# KX1_DB_DAC_2.net
KiCad netlist of a schematic drawn in Altium Designer
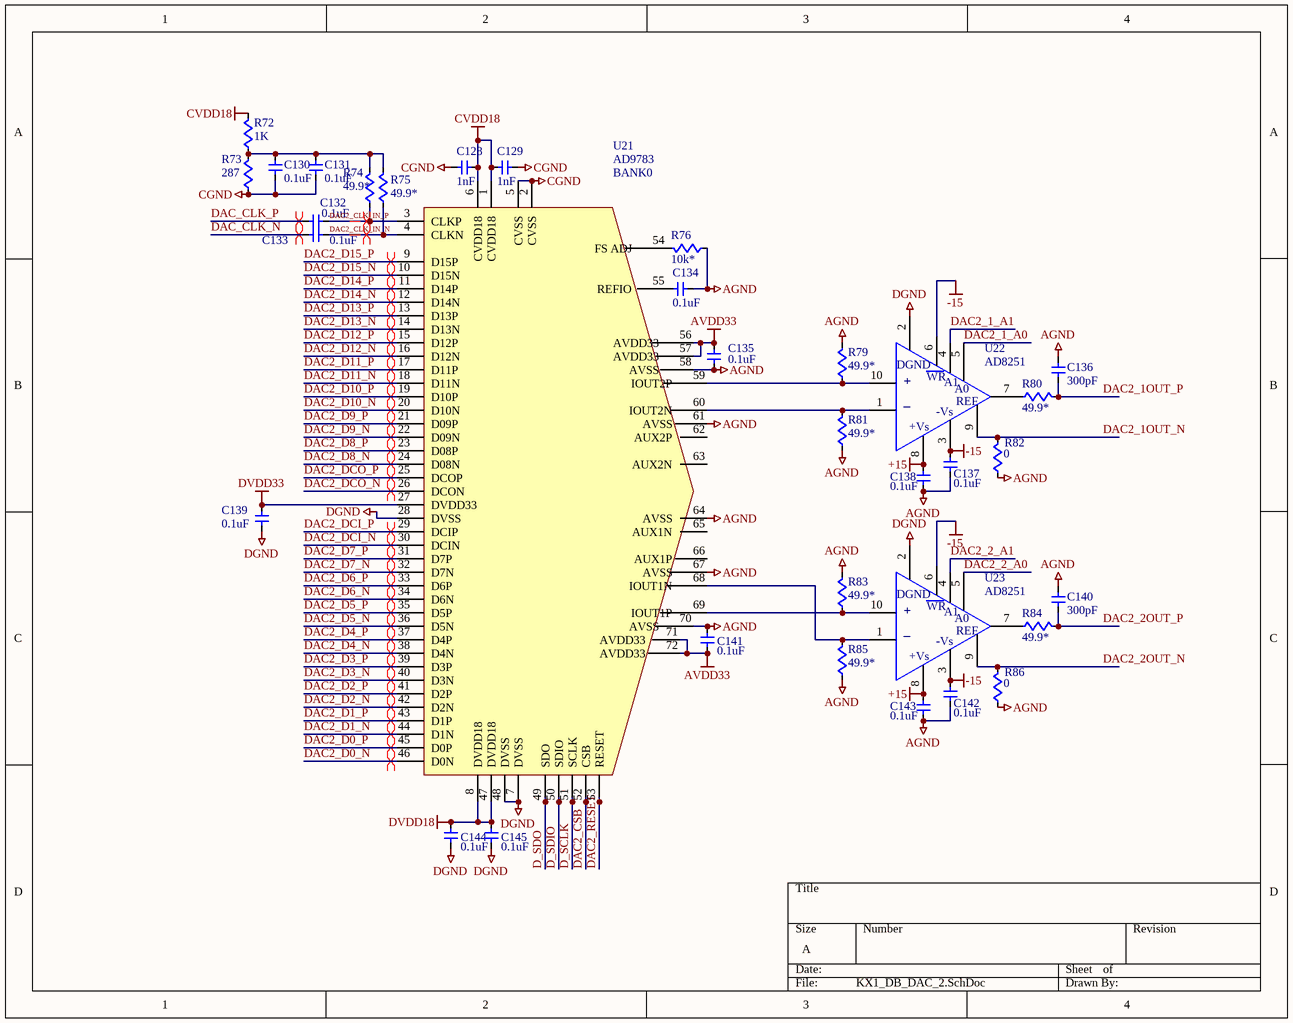
[diagram p0: KX1_DB_DAC_2.SchDoc]

(export (version "E")
  (design (tool "Eeschema 10.0.6"))
  (components
    (comp (ref "C128")
      (value "1nF")
      (footprint "0603w")
      (description "capacitor")
      (fields
        (field (name "MANUFACTURER") "Murata Electronics North America")
        (field (name "MANUFACTURER PART NUMBER") "GRM188R71H102KA01D")
      )
      (libsource (lib "KX1_DB") (part "CAP_SM_1"))
    )
    (comp (ref "C129")
      (value "1nF")
      (footprint "0603w")
      (description "capacitor")
      (fields
        (field (name "MANUFACTURER") "Murata Electronics North America")
        (field (name "MANUFACTURER PART NUMBER") "GRM188R71H102KA01D")
      )
      (libsource (lib "KX1_DB") (part "CAP_SM_1"))
    )
    (comp (ref "C130")
      (value "0.1uF")
      (footprint "0603w")
      (description "capacitor")
      (fields
        (field (name "MANUFACTURER") "Kemet")
        (field (name "MANUFACTURER PART NUMBER") "C0603C104K3RACTU")
      )
      (libsource (lib "KX1_DB") (part "CAP_SM"))
    )
    (comp (ref "C131")
      (value "0.1uF")
      (footprint "0603w")
      (description "capacitor")
      (fields
        (field (name "MANUFACTURER") "Kemet")
        (field (name "MANUFACTURER PART NUMBER") "C0603C104K3RACTU")
      )
      (libsource (lib "KX1_DB") (part "CAP_SM"))
    )
    (comp (ref "C132")
      (value "0.1uF")
      (footprint "1206")
      (description "capacitor")
      (fields
        (field (name "MANUFACTURER") "Murata Electronics North America")
        (field (name "MANUFACTURER PART NUMBER") "GRM31C5C1E104JA01L")
      )
      (libsource (lib "KX1_DB") (part "CAP_SM_1"))
    )
    (comp (ref "C133")
      (value "0.1uF")
      (footprint "1206")
      (description "capacitor")
      (fields
        (field (name "MANUFACTURER") "Murata Electronics North America")
        (field (name "MANUFACTURER PART NUMBER") "GRM31C5C1E104JA01L")
      )
      (libsource (lib "KX1_DB") (part "CAP_SM_1"))
    )
    (comp (ref "C134")
      (value "0.1uF")
      (footprint "0603w")
      (description "capacitor")
      (fields
        (field (name "MANUFACTURER") "Kemet")
        (field (name "MANUFACTURER PART NUMBER") "C0603C104K3RACTU")
      )
      (libsource (lib "KX1_DB") (part "CAP_SM_1"))
    )
    (comp (ref "C135")
      (value "0.1uF")
      (footprint "0603w")
      (description "capacitor")
      (fields
        (field (name "MANUFACTURER") "Kemet")
        (field (name "MANUFACTURER PART NUMBER") "C0603C104K3RACTU")
      )
      (libsource (lib "KX1_DB") (part "CAP_SM_1"))
    )
    (comp (ref "C136")
      (value "300pF")
      (footprint "0603w")
      (description "capacitor")
      (libsource (lib "KX1_DB") (part "CAP_SM_1"))
    )
    (comp (ref "C137")
      (value "0.1uF")
      (footprint "0603w")
      (description "capacitor")
      (fields
        (field (name "MANUFACTURER") "Kemet")
        (field (name "MANUFACTURER PART NUMBER") "C0603C104K3RACTU")
      )
      (libsource (lib "KX1_DB") (part "CAP_SM_1"))
    )
    (comp (ref "C138")
      (value "0.1uF")
      (footprint "0603w")
      (description "capacitor")
      (fields
        (field (name "MANUFACTURER") "Kemet")
        (field (name "MANUFACTURER PART NUMBER") "C0603C104K3RACTU")
      )
      (libsource (lib "KX1_DB") (part "CAP_SM_1"))
    )
    (comp (ref "C139")
      (value "0.1uF")
      (footprint "0603w")
      (description "capacitor")
      (fields
        (field (name "MANUFACTURER") "Kemet")
        (field (name "MANUFACTURER PART NUMBER") "C0603C104K3RACTU")
      )
      (libsource (lib "KX1_DB") (part "CAP_SM_1"))
    )
    (comp (ref "C140")
      (value "300pF")
      (footprint "0603w")
      (description "capacitor")
      (libsource (lib "KX1_DB") (part "CAP_SM_1"))
    )
    (comp (ref "C141")
      (value "0.1uF")
      (footprint "0603w")
      (description "capacitor")
      (fields
        (field (name "MANUFACTURER") "Kemet")
        (field (name "MANUFACTURER PART NUMBER") "C0603C104K3RACTU")
      )
      (libsource (lib "KX1_DB") (part "CAP_SM_1"))
    )
    (comp (ref "C142")
      (value "0.1uF")
      (footprint "0603w")
      (description "capacitor")
      (fields
        (field (name "MANUFACTURER") "Kemet")
        (field (name "MANUFACTURER PART NUMBER") "C0603C104K3RACTU")
      )
      (libsource (lib "KX1_DB") (part "CAP_SM_1"))
    )
    (comp (ref "C143")
      (value "0.1uF")
      (footprint "0603w")
      (description "capacitor")
      (fields
        (field (name "MANUFACTURER") "Kemet")
        (field (name "MANUFACTURER PART NUMBER") "C0603C104K3RACTU")
      )
      (libsource (lib "KX1_DB") (part "CAP_SM_1"))
    )
    (comp (ref "C144")
      (value "0.1uF")
      (footprint "0603w")
      (description "capacitor")
      (fields
        (field (name "MANUFACTURER") "Kemet")
        (field (name "MANUFACTURER PART NUMBER") "C0603C104K3RACTU")
      )
      (libsource (lib "KX1_DB") (part "CAP_SM_1"))
    )
    (comp (ref "C145")
      (value "0.1uF")
      (footprint "0603w")
      (description "capacitor")
      (fields
        (field (name "MANUFACTURER") "Kemet")
        (field (name "MANUFACTURER PART NUMBER") "C0603C104K3RACTU")
      )
      (libsource (lib "KX1_DB") (part "CAP_SM_1"))
    )
    (comp (ref "R72")
      (value "1K")
      (footprint "0603w")
      (description "resistor")
      (fields
        (field (name "MANUFACTURER") "Yageo")
        (field (name "MANUFACTURER PART NUMBER") "RC0603FR-071KL")
      )
      (libsource (lib "KX1_DB") (part "RES_SM"))
    )
    (comp (ref "R73")
      (value "287")
      (footprint "0603w")
      (description "resistor")
      (fields
        (field (name "MANUFACTURER") "Yageo")
        (field (name "MANUFACTURER PART NUMBER") "RC0603FR-07287RL")
      )
      (libsource (lib "KX1_DB") (part "RES_SM"))
    )
    (comp (ref "R74")
      (value "49.9*")
      (footprint "0603w")
      (description "resistor")
      (fields
        (field (name "MANUFACTURER") "Stackpole Electronics Inc")
        (field (name "MANUFACTURER PART NUMBER") "RNCS0603BKE49R9")
      )
      (libsource (lib "KX1_DB") (part "RES_SM"))
    )
    (comp (ref "R75")
      (value "49.9*")
      (footprint "0603w")
      (description "resistor")
      (fields
        (field (name "MANUFACTURER") "Stackpole Electronics Inc")
        (field (name "MANUFACTURER PART NUMBER") "RNCS0603BKE49R9")
      )
      (libsource (lib "KX1_DB") (part "RES_SM"))
    )
    (comp (ref "R76")
      (value "10k*")
      (footprint "0603w")
      (description "resistor")
      (fields
        (field (name "MANUFACTURER") "Susumu")
        (field (name "MANUFACTURER PART NUMBER") "RG1608P-103-B-T5")
      )
      (libsource (lib "KX1_DB") (part "RES_SM"))
    )
    (comp (ref "R79")
      (value "49.9*")
      (footprint "0603w")
      (description "resistor")
      (fields
        (field (name "MANUFACTURER") "Stackpole Electronics Inc")
        (field (name "MANUFACTURER PART NUMBER") "RNCS0603BKE49R9")
      )
      (libsource (lib "KX1_DB") (part "RES_SM"))
    )
    (comp (ref "R80")
      (value "49.9*")
      (footprint "0603w")
      (description "resistor")
      (fields
        (field (name "MANUFACTURER") "Stackpole Electronics Inc")
        (field (name "MANUFACTURER PART NUMBER") "RNCS0603BKE49R9")
      )
      (libsource (lib "KX1_DB") (part "RES_SM"))
    )
    (comp (ref "R81")
      (value "49.9*")
      (footprint "0603w")
      (description "resistor")
      (fields
        (field (name "MANUFACTURER") "Stackpole Electronics Inc")
        (field (name "MANUFACTURER PART NUMBER") "RNCS0603BKE49R9")
      )
      (libsource (lib "KX1_DB") (part "RES_SM"))
    )
    (comp (ref "R82")
      (value "0")
      (footprint "0603w")
      (description "resistor")
      (libsource (lib "KX1_DB") (part "RES_SM"))
    )
    (comp (ref "R83")
      (value "49.9*")
      (footprint "0603w")
      (description "resistor")
      (fields
        (field (name "MANUFACTURER") "Stackpole Electronics Inc")
        (field (name "MANUFACTURER PART NUMBER") "RNCS0603BKE49R9")
      )
      (libsource (lib "KX1_DB") (part "RES_SM"))
    )
    (comp (ref "R84")
      (value "49.9*")
      (footprint "0603w")
      (description "resistor")
      (fields
        (field (name "MANUFACTURER") "Stackpole Electronics Inc")
        (field (name "MANUFACTURER PART NUMBER") "RNCS0603BKE49R9")
      )
      (libsource (lib "KX1_DB") (part "RES_SM"))
    )
    (comp (ref "R85")
      (value "49.9*")
      (footprint "0603w")
      (description "resistor")
      (fields
        (field (name "MANUFACTURER") "Stackpole Electronics Inc")
        (field (name "MANUFACTURER PART NUMBER") "RNCS0603BKE49R9")
      )
      (libsource (lib "KX1_DB") (part "RES_SM"))
    )
    (comp (ref "R86")
      (value "0")
      (footprint "0603w")
      (description "resistor")
      (libsource (lib "KX1_DB") (part "RES_SM"))
    )
    (comp (ref "U21")
      (value "AD9783")
      (footprint "LFCSP72")
      (description "DAC LVDS DUAL16BIT 500MSPS")
      (libsource (lib "KX1_DB") (part "AD9783"))
    )
    (comp (ref "U22")
      (value "AD8251")
      (footprint "MSOP10sm")
      (description "IC AMP INST ICMOS LDRIFT 10MSOP")
      (libsource (lib "KX1_DB") (part "AD8251"))
    )
    (comp (ref "U23")
      (value "AD8251")
      (footprint "MSOP10sm")
      (description "IC AMP INST ICMOS LDRIFT 10MSOP")
      (libsource (lib "KX1_DB") (part "AD8251"))
    )
  )
  (nets
    (net (code "1") (name "+15") (class "Default")
      (node (ref "C138") (pin "2") (pintype "passive"))
      (node (ref "C143") (pin "2") (pintype "passive"))
      (node (ref "U22") (pin "8") (pintype "passive"))
      (node (ref "U23") (pin "8") (pintype "passive"))
    )
    (net (code "2") (name "-15") (class "Default")
      (node (ref "C137") (pin "2") (pintype "passive"))
      (node (ref "C142") (pin "2") (pintype "passive"))
      (node (ref "U22") (pin "3") (pintype "passive"))
      (node (ref "U22") (pin "6") (pintype "passive"))
      (node (ref "U23") (pin "3") (pintype "passive"))
      (node (ref "U23") (pin "6") (pintype "passive"))
    )
    (net (code "3") (name "/DAC2_1OUT_N") (class "Default")
      (node (ref "R82") (pin "2") (pintype "passive"))
      (node (ref "U22") (pin "9") (pintype "passive"))
    )
    (net (code "4") (name "/DAC2_1OUT_P") (class "Default")
      (node (ref "C136") (pin "1") (pintype "passive"))
      (node (ref "R80") (pin "2") (pintype "passive"))
    )
    (net (code "5") (name "/DAC2_1_A0") (class "Default") (node (ref "U22") (pin "5") (pintype "passive")))
    (net (code "6") (name "/DAC2_1_A1") (class "Default") (node (ref "U22") (pin "4") (pintype "passive")))
    (net (code "7") (name "/DAC2_2OUT_N") (class "Default")
      (node (ref "R86") (pin "2") (pintype "passive"))
      (node (ref "U23") (pin "9") (pintype "passive"))
    )
    (net (code "8") (name "/DAC2_2OUT_P") (class "Default")
      (node (ref "C140") (pin "1") (pintype "passive"))
      (node (ref "R84") (pin "2") (pintype "passive"))
    )
    (net (code "9") (name "/DAC2_2_A0") (class "Default") (node (ref "U23") (pin "5") (pintype "passive")))
    (net (code "10") (name "/DAC2_2_A1") (class "Default") (node (ref "U23") (pin "4") (pintype "passive")))
    (net (code "11") (name "/DAC2_CLK_IN_N") (class "Default")
      (node (ref "C133") (pin "2") (pintype "passive"))
      (node (ref "R75") (pin "1") (pintype "passive"))
      (node (ref "U21") (pin "4") (pinfunction "CLKN_4") (pintype "passive"))
    )
    (net (code "12") (name "/DAC2_CLK_IN_P") (class "Default")
      (node (ref "C132") (pin "2") (pintype "passive"))
      (node (ref "R74") (pin "1") (pintype "passive"))
      (node (ref "U21") (pin "3") (pinfunction "CLKP_3") (pintype "passive"))
    )
    (net (code "13") (name "/DAC2_CSB") (class "Default")
      (node (ref "U21") (pin "52") (pinfunction "CSB_52") (pintype "passive"))
    )
    (net (code "14") (name "/DAC2_D0_N") (class "Default")
      (node (ref "U21") (pin "46") (pinfunction "D0N_46") (pintype "passive"))
    )
    (net (code "15") (name "/DAC2_D0_P") (class "Default")
      (node (ref "U21") (pin "45") (pinfunction "D0P_45") (pintype "passive"))
    )
    (net (code "16") (name "/DAC2_D1_N") (class "Default")
      (node (ref "U21") (pin "44") (pinfunction "D1N_44") (pintype "passive"))
    )
    (net (code "17") (name "/DAC2_D1_P") (class "Default")
      (node (ref "U21") (pin "43") (pinfunction "D1P_43") (pintype "passive"))
    )
    (net (code "18") (name "/DAC2_D2_N") (class "Default")
      (node (ref "U21") (pin "42") (pinfunction "D2N_42") (pintype "passive"))
    )
    (net (code "19") (name "/DAC2_D2_P") (class "Default")
      (node (ref "U21") (pin "41") (pinfunction "D2P_41") (pintype "passive"))
    )
    (net (code "20") (name "/DAC2_D3_N") (class "Default")
      (node (ref "U21") (pin "40") (pinfunction "D3N_40") (pintype "passive"))
    )
    (net (code "21") (name "/DAC2_D3_P") (class "Default")
      (node (ref "U21") (pin "39") (pinfunction "D3P_39") (pintype "passive"))
    )
    (net (code "22") (name "/DAC2_D4_N") (class "Default")
      (node (ref "U21") (pin "38") (pinfunction "D4N_38") (pintype "passive"))
    )
    (net (code "23") (name "/DAC2_D4_P") (class "Default")
      (node (ref "U21") (pin "37") (pinfunction "D4P_37") (pintype "passive"))
    )
    (net (code "24") (name "/DAC2_D5_N") (class "Default")
      (node (ref "U21") (pin "36") (pinfunction "D5N_36") (pintype "passive"))
    )
    (net (code "25") (name "/DAC2_D5_P") (class "Default")
      (node (ref "U21") (pin "35") (pinfunction "D5P_35") (pintype "passive"))
    )
    (net (code "26") (name "/DAC2_D6_N") (class "Default")
      (node (ref "U21") (pin "34") (pinfunction "D6N_34") (pintype "passive"))
    )
    (net (code "27") (name "/DAC2_D6_P") (class "Default")
      (node (ref "U21") (pin "33") (pinfunction "D6P_33") (pintype "passive"))
    )
    (net (code "28") (name "/DAC2_D7_N") (class "Default")
      (node (ref "U21") (pin "32") (pinfunction "D7N_32") (pintype "passive"))
    )
    (net (code "29") (name "/DAC2_D7_P") (class "Default")
      (node (ref "U21") (pin "31") (pinfunction "D7P_31") (pintype "passive"))
    )
    (net (code "30") (name "/DAC2_D8_N") (class "Default")
      (node (ref "U21") (pin "24") (pinfunction "D08N_24") (pintype "passive"))
    )
    (net (code "31") (name "/DAC2_D8_P") (class "Default")
      (node (ref "U21") (pin "23") (pinfunction "D08P_23") (pintype "passive"))
    )
    (net (code "32") (name "/DAC2_D9_N") (class "Default")
      (node (ref "U21") (pin "22") (pinfunction "D09N_22") (pintype "passive"))
    )
    (net (code "33") (name "/DAC2_D9_P") (class "Default")
      (node (ref "U21") (pin "21") (pinfunction "D09P_21") (pintype "passive"))
    )
    (net (code "34") (name "/DAC2_D10_N") (class "Default")
      (node (ref "U21") (pin "20") (pinfunction "D10N_20") (pintype "passive"))
    )
    (net (code "35") (name "/DAC2_D10_P") (class "Default")
      (node (ref "U21") (pin "19") (pinfunction "D10P_19") (pintype "passive"))
    )
    (net (code "36") (name "/DAC2_D11_N") (class "Default")
      (node (ref "U21") (pin "18") (pinfunction "D11N_18") (pintype "passive"))
    )
    (net (code "37") (name "/DAC2_D11_P") (class "Default")
      (node (ref "U21") (pin "17") (pinfunction "D11P_17") (pintype "passive"))
    )
    (net (code "38") (name "/DAC2_D12_N") (class "Default")
      (node (ref "U21") (pin "16") (pinfunction "D12N_16") (pintype "passive"))
    )
    (net (code "39") (name "/DAC2_D12_P") (class "Default")
      (node (ref "U21") (pin "15") (pinfunction "D12P_15") (pintype "passive"))
    )
    (net (code "40") (name "/DAC2_D13_N") (class "Default")
      (node (ref "U21") (pin "14") (pinfunction "D13N_14") (pintype "passive"))
    )
    (net (code "41") (name "/DAC2_D13_P") (class "Default")
      (node (ref "U21") (pin "13") (pinfunction "D13P_13") (pintype "passive"))
    )
    (net (code "42") (name "/DAC2_D14_N") (class "Default")
      (node (ref "U21") (pin "12") (pinfunction "D14N_12") (pintype "passive"))
    )
    (net (code "43") (name "/DAC2_D14_P") (class "Default")
      (node (ref "U21") (pin "11") (pinfunction "D14P_11") (pintype "passive"))
    )
    (net (code "44") (name "/DAC2_D15_N") (class "Default")
      (node (ref "U21") (pin "10") (pinfunction "D15N_10") (pintype "passive"))
    )
    (net (code "45") (name "/DAC2_D15_P") (class "Default")
      (node (ref "U21") (pin "9") (pinfunction "D15P_9") (pintype "passive"))
    )
    (net (code "46") (name "/DAC2_DCI_N") (class "Default")
      (node (ref "U21") (pin "30") (pinfunction "DCIN_30") (pintype "passive"))
    )
    (net (code "47") (name "/DAC2_DCI_P") (class "Default")
      (node (ref "U21") (pin "29") (pinfunction "DCIP_29") (pintype "passive"))
    )
    (net (code "48") (name "/DAC2_DCO_N") (class "Default")
      (node (ref "U21") (pin "26") (pinfunction "DCON_26") (pintype "passive"))
    )
    (net (code "49") (name "/DAC2_DCO_P") (class "Default")
      (node (ref "U21") (pin "25") (pinfunction "DCOP_25") (pintype "passive"))
    )
    (net (code "50") (name "/DAC2_RESET") (class "Default")
      (node (ref "U21") (pin "53") (pinfunction "RESET_53") (pintype "passive"))
    )
    (net (code "51") (name "/DAC_CLK_N") (class "Default") (node (ref "C133") (pin "1") (pintype "passive")))
    (net (code "52") (name "/DAC_CLK_P") (class "Default") (node (ref "C132") (pin "1") (pintype "passive")))
    (net (code "53") (name "/D_SCLK") (class "Default")
      (node (ref "U21") (pin "51") (pinfunction "SCLK_51") (pintype "passive"))
    )
    (net (code "54") (name "/D_SDIO") (class "Default")
      (node (ref "U21") (pin "50") (pinfunction "SDIO_50") (pintype "passive"))
    )
    (net (code "55") (name "/D_SDO") (class "Default")
      (node (ref "U21") (pin "49") (pinfunction "SDO_49") (pintype "passive"))
    )
    (net (code "56") (name "AGND") (class "Default")
      (node (ref "C134") (pin "2") (pintype "passive"))
      (node (ref "C135") (pin "1") (pintype "passive"))
      (node (ref "C136") (pin "2") (pintype "passive"))
      (node (ref "C137") (pin "1") (pintype "passive"))
      (node (ref "C138") (pin "1") (pintype "passive"))
      (node (ref "C140") (pin "2") (pintype "passive"))
      (node (ref "C141") (pin "2") (pintype "passive"))
      (node (ref "C142") (pin "1") (pintype "passive"))
      (node (ref "C143") (pin "1") (pintype "passive"))
      (node (ref "R76") (pin "1") (pintype "passive"))
      (node (ref "R79") (pin "2") (pintype "passive"))
      (node (ref "R81") (pin "1") (pintype "passive"))
      (node (ref "R82") (pin "1") (pintype "passive"))
      (node (ref "R83") (pin "2") (pintype "passive"))
      (node (ref "R85") (pin "1") (pintype "passive"))
      (node (ref "R86") (pin "1") (pintype "passive"))
      (node (ref "U21") (pin "58") (pinfunction "AVSS_58") (pintype "passive"))
      (node (ref "U21") (pin "61") (pinfunction "AVSS_61") (pintype "passive"))
      (node (ref "U21") (pin "64") (pinfunction "AVSS_64") (pintype "passive"))
      (node (ref "U21") (pin "67") (pinfunction "AVSS_67") (pintype "passive"))
      (node (ref "U21") (pin "70") (pinfunction "AVSS_70") (pintype "passive"))
    )
    (net (code "57") (name "AVDD33") (class "Default")
      (node (ref "C135") (pin "2") (pintype "passive"))
      (node (ref "C141") (pin "1") (pintype "passive"))
      (node (ref "U21") (pin "56") (pinfunction "AVDD33_56") (pintype "passive"))
      (node (ref "U21") (pin "57") (pinfunction "AVDD33_57") (pintype "passive"))
      (node (ref "U21") (pin "71") (pinfunction "AVDD33_71") (pintype "passive"))
      (node (ref "U21") (pin "72") (pinfunction "AVDD33_72") (pintype "passive"))
    )
    (net (code "58") (name "CGND") (class "Default")
      (node (ref "C128") (pin "2") (pintype "passive"))
      (node (ref "C129") (pin "2") (pintype "passive"))
      (node (ref "C130") (pin "2") (pintype "passive"))
      (node (ref "C131") (pin "2") (pintype "passive"))
      (node (ref "R73") (pin "1") (pintype "passive"))
      (node (ref "U21") (pin "2") (pinfunction "CVSS_2") (pintype "passive"))
      (node (ref "U21") (pin "5") (pinfunction "CVSS_5") (pintype "passive"))
    )
    (net (code "59") (name "CVDD18") (class "Default")
      (node (ref "C128") (pin "1") (pintype "passive"))
      (node (ref "C129") (pin "1") (pintype "passive"))
      (node (ref "R72") (pin "2") (pintype "passive"))
      (node (ref "U21") (pin "1") (pinfunction "CVDD18_1") (pintype "passive"))
      (node (ref "U21") (pin "6") (pinfunction "CVDD18_6") (pintype "passive"))
    )
    (net (code "60") (name "DGND") (class "Default")
      (node (ref "C139") (pin "2") (pintype "passive"))
      (node (ref "C144") (pin "1") (pintype "passive"))
      (node (ref "C145") (pin "1") (pintype "passive"))
      (node (ref "U21") (pin "28") (pinfunction "DVSS_28") (pintype "passive"))
      (node (ref "U21") (pin "48") (pinfunction "DVSS_48") (pintype "passive"))
      (node (ref "U21") (pin "7") (pinfunction "DVSS_7") (pintype "passive"))
      (node (ref "U22") (pin "2") (pintype "passive"))
      (node (ref "U23") (pin "2") (pintype "passive"))
    )
    (net (code "61") (name "DVDD18") (class "Default")
      (node (ref "C144") (pin "2") (pintype "passive"))
      (node (ref "C145") (pin "2") (pintype "passive"))
      (node (ref "U21") (pin "47") (pinfunction "DVDD18_47") (pintype "passive"))
      (node (ref "U21") (pin "8") (pinfunction "DVDD18_8") (pintype "passive"))
    )
    (net (code "62") (name "DVDD33") (class "Default")
      (node (ref "C139") (pin "1") (pintype "passive"))
      (node (ref "U21") (pin "27") (pinfunction "DVDD33_27") (pintype "passive"))
    )
    (net (code "63") (name "Net-(C130-Pad1)") (class "Default")
      (node (ref "C130") (pin "1") (pintype "passive"))
      (node (ref "C131") (pin "1") (pintype "passive"))
      (node (ref "R72") (pin "1") (pintype "passive"))
      (node (ref "R73") (pin "2") (pintype "passive"))
      (node (ref "R74") (pin "2") (pintype "passive"))
      (node (ref "R75") (pin "2") (pintype "passive"))
    )
    (net (code "64") (name "Net-(R80-Pad1)") (class "Default")
      (node (ref "R80") (pin "1") (pintype "passive"))
      (node (ref "U22") (pin "7") (pintype "passive"))
    )
    (net (code "65") (name "Net-(R84-Pad1)") (class "Default")
      (node (ref "R84") (pin "1") (pintype "passive"))
      (node (ref "U23") (pin "7") (pintype "passive"))
    )
    (net (code "66") (name "Net-(U21-FS_ADJ)") (class "Default")
      (node (ref "R76") (pin "2") (pintype "passive"))
      (node (ref "U21") (pin "54") (pinfunction "FS_ADJ_54") (pintype "passive"))
    )
    (net (code "67") (name "Net-(U21-IOUT1N)") (class "Default")
      (node (ref "R85") (pin "2") (pintype "passive"))
      (node (ref "U21") (pin "68") (pinfunction "IOUT1N_68") (pintype "passive"))
      (node (ref "U23") (pin "1") (pintype "passive"))
    )
    (net (code "68") (name "Net-(U21-IOUT1P)") (class "Default")
      (node (ref "R83") (pin "1") (pintype "passive"))
      (node (ref "U21") (pin "69") (pinfunction "IOUT1P_69") (pintype "passive"))
      (node (ref "U23") (pin "10") (pintype "passive"))
    )
    (net (code "69") (name "Net-(U21-IOUT2N)") (class "Default")
      (node (ref "R81") (pin "2") (pintype "passive"))
      (node (ref "U21") (pin "60") (pinfunction "IOUT2N_60") (pintype "passive"))
      (node (ref "U22") (pin "1") (pintype "passive"))
    )
    (net (code "70") (name "Net-(U21-IOUT2P)") (class "Default")
      (node (ref "R79") (pin "1") (pintype "passive"))
      (node (ref "U21") (pin "59") (pinfunction "IOUT2P_59") (pintype "passive"))
      (node (ref "U22") (pin "10") (pintype "passive"))
    )
    (net (code "71") (name "Net-(U21-REFIO)") (class "Default")
      (node (ref "C134") (pin "1") (pintype "passive"))
      (node (ref "U21") (pin "55") (pinfunction "REFIO_55") (pintype "passive"))
    )
    (net (code "72") (name "unconnected-(U21-AUX1N-Pad65)") (class "Default")
      (node (ref "U21") (pin "65") (pinfunction "AUX1N_65") (pintype "passive"))
    )
    (net (code "73") (name "unconnected-(U21-AUX1P-Pad66)") (class "Default")
      (node (ref "U21") (pin "66") (pinfunction "AUX1P_66") (pintype "passive"))
    )
    (net (code "74") (name "unconnected-(U21-AUX2N-Pad63)") (class "Default")
      (node (ref "U21") (pin "63") (pinfunction "AUX2N_63") (pintype "passive"))
    )
    (net (code "75") (name "unconnected-(U21-AUX2P-Pad62)") (class "Default")
      (node (ref "U21") (pin "62") (pinfunction "AUX2P_62") (pintype "passive"))
    )
  )
)
